# Charger.net
KiCad netlist of a schematic drawn in Altium Designer
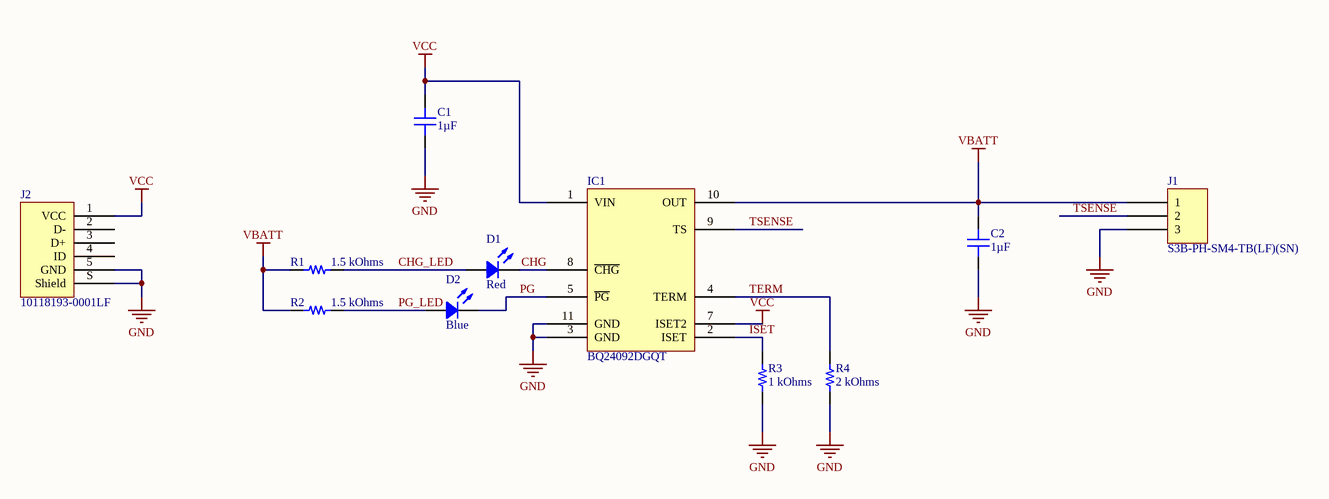
[diagram p0: Charger.SchDoc]

(export (version "E")
  (design (tool "Eeschema 10.0.6"))
  (components
    (comp (ref "C1")
      (value "1µF")
      (footprint "CAP 0603_1608")
      (description "CAP CER 1UF 25V X5R 0603")
      (fields (field (name "PART NUMBER") "CC0603KRX5R8BB105") (field (name "MANUFACTURER") "Yageo"))
      (libsource (lib "Celestial Altium Library - altium_library") (part "Capacitor"))
    )
    (comp (ref "C2")
      (value "1µF")
      (footprint "CAP 0603_1608")
      (description "CAP CER 1UF 25V X5R 0603")
      (fields (field (name "PART NUMBER") "CC0603KRX5R8BB105") (field (name "MANUFACTURER") "Yageo"))
      (libsource (lib "Celestial Altium Library - altium_library") (part "Capacitor"))
    )
    (comp (ref "D1")
      (value "Red")
      (footprint "LED 0603_1608 RED")
      (description "LED RED CLEAR 2SMD")
      (fields
        (field (name "PART NUMBER") "19-213USRC/S259/TR8")
        (field (name "MANUFACTURER") "Everlight Electronics Co Ltd")
      )
      (libsource (lib "Celestial Altium Library - altium_library") (part "LED"))
    )
    (comp (ref "D2")
      (value "Blue")
      (footprint "LED 0603_1608 BLUE")
      (description "LED BLUE CLEAR 2SMD")
      (fields
        (field (name "PART NUMBER") "EAST16084BA8")
        (field (name "MANUFACTURER") "Everlight Electronics Co Ltd")
      )
      (libsource (lib "Celestial Altium Library - altium_library") (part "LED"))
    )
    (comp (ref "IC1")
      (value "BQ24092DGQT")
      (footprint "TI PDSO-10 DCQ")
      (description "IC BATT CHARGER LI-ION 10MSOP")
      (fields (field (name "MANUFACTURER") "Texas Instruments"))
      (libsource (lib "Celestial Altium Library - altium_library") (part "TI BQ2409x"))
    )
    (comp (ref "J1")
      (value "S3B-PH-SM4-TB(LF)(SN)")
      (footprint "JST S3B-PH-SM4-TB")
      (description "CONN HEADER SMD R/A 3POS 2MM")
      (fields (field (name "MANUFACTURER") "JST Sales America Inc."))
      (libsource (lib "Celestial Altium Library - altium_library") (part "3 Pin"))
    )
    (comp (ref "J2")
      (value "10118193-0001LF")
      (footprint "FCI USB 10118193-0001LF")
      (description "CONN RCPT USB2.0 MICRO B SMD R/A")
      (fields (field (name "MANUFACTURER") "Amphenol ICC (FCI)"))
      (libsource (lib "Celestial Altium Library - altium_library") (part "USB 2.0 Type B Micro"))
    )
    (comp (ref "R1")
      (value "1.5 kOhms")
      (footprint "RES 0603_1608")
      (description "RES SMD 1.5K OHM 1% 1/10W 0603")
      (fields
        (field (name "PART NUMBER") "ERJ-3EKF1501V")
        (field (name "MANUFACTURER") "Panasonic Electronic Components")
      )
      (libsource (lib "Celestial Altium Library - altium_library") (part "Resistor"))
    )
    (comp (ref "R2")
      (value "1.5 kOhms")
      (footprint "RES 0603_1608")
      (description "RES SMD 1.5K OHM 1% 1/10W 0603")
      (fields
        (field (name "PART NUMBER") "ERJ-3EKF1501V")
        (field (name "MANUFACTURER") "Panasonic Electronic Components")
      )
      (libsource (lib "Celestial Altium Library - altium_library") (part "Resistor"))
    )
    (comp (ref "R3")
      (value "1 kOhms")
      (footprint "RES 0603_1608")
      (description "RES SMD 1K OHM 5% 1/4W 0603")
      (fields
        (field (name "PART NUMBER") "ERJ-PA3J102V")
        (field (name "MANUFACTURER") "Panasonic Electronic Components")
      )
      (libsource (lib "Celestial Altium Library - altium_library") (part "Resistor"))
    )
    (comp (ref "R4")
      (value "2 kOhms")
      (footprint "RES 0603_1608")
      (description "RES SMD 2K OHM 5% 1/4W 0603")
      (fields
        (field (name "PART NUMBER") "ERJ-PA3J202V")
        (field (name "MANUFACTURER") "Panasonic Electronic Components")
      )
      (libsource (lib "Celestial Altium Library - altium_library") (part "Resistor"))
    )
  )
  (nets
    (net (code "1") (name "/CHG") (class "Default")
      (node (ref "D1") (pin "2") (pinfunction "2_2") (pintype "passive"))
      (node (ref "IC1") (pin "8") (pinfunction "~{CHG}_8") (pintype "passive"))
    )
    (net (code "2") (name "/CHG_LED") (class "Default")
      (node (ref "D1") (pin "1") (pinfunction "1_1") (pintype "passive"))
      (node (ref "R1") (pin "2") (pinfunction "2_2") (pintype "passive"))
    )
    (net (code "3") (name "/ISET") (class "Default")
      (node (ref "IC1") (pin "2") (pinfunction "ISET_2") (pintype "passive"))
      (node (ref "R3") (pin "2") (pinfunction "2_2") (pintype "passive"))
    )
    (net (code "4") (name "/PG") (class "Default")
      (node (ref "D2") (pin "2") (pinfunction "2_2") (pintype "passive"))
      (node (ref "IC1") (pin "5") (pinfunction "~{PG}_5") (pintype "passive"))
    )
    (net (code "5") (name "/PG_LED") (class "Default")
      (node (ref "D2") (pin "1") (pinfunction "1_1") (pintype "passive"))
      (node (ref "R2") (pin "2") (pinfunction "2_2") (pintype "passive"))
    )
    (net (code "6") (name "/TERM") (class "Default")
      (node (ref "IC1") (pin "4") (pinfunction "TERM_4") (pintype "passive"))
      (node (ref "R4") (pin "2") (pinfunction "2_2") (pintype "passive"))
    )
    (net (code "7") (name "/TSENSE") (class "Default")
      (node (ref "IC1") (pin "9") (pinfunction "TS_9") (pintype "passive"))
      (node (ref "J1") (pin "2") (pinfunction "2_2") (pintype "passive"))
    )
    (net (code "8") (name "GND") (class "Default")
      (node (ref "C1") (pin "1") (pinfunction "1_1") (pintype "passive"))
      (node (ref "C2") (pin "1") (pinfunction "1_1") (pintype "passive"))
      (node (ref "IC1") (pin "11") (pinfunction "GND_11") (pintype "passive"))
      (node (ref "IC1") (pin "3") (pinfunction "GND_3") (pintype "passive"))
      (node (ref "J1") (pin "3") (pinfunction "3_3") (pintype "passive"))
      (node (ref "J2") (pin "5") (pinfunction "GND_5") (pintype "passive"))
      (node (ref "J2") (pin "S") (pinfunction "Shield_S") (pintype "passive"))
      (node (ref "R3") (pin "1") (pinfunction "1_1") (pintype "passive"))
      (node (ref "R4") (pin "1") (pinfunction "1_1") (pintype "passive"))
    )
    (net (code "9") (name "VBATT") (class "Default")
      (node (ref "C2") (pin "2") (pinfunction "2_2") (pintype "passive"))
      (node (ref "IC1") (pin "10") (pinfunction "OUT_10") (pintype "passive"))
      (node (ref "J1") (pin "1") (pinfunction "1_1") (pintype "passive"))
      (node (ref "R1") (pin "1") (pinfunction "1_1") (pintype "passive"))
      (node (ref "R2") (pin "1") (pinfunction "1_1") (pintype "passive"))
    )
    (net (code "10") (name "VCC") (class "Default")
      (node (ref "C1") (pin "2") (pinfunction "2_2") (pintype "passive"))
      (node (ref "IC1") (pin "1") (pinfunction "VIN_1") (pintype "passive"))
      (node (ref "IC1") (pin "7") (pinfunction "ISET2_7") (pintype "passive"))
      (node (ref "J2") (pin "1") (pinfunction "VCC_1") (pintype "passive"))
    )
    (net (code "11") (name "unconnected-(J2-D+-Pad3)") (class "Default")
      (node (ref "J2") (pin "3") (pinfunction "D+_3") (pintype "passive"))
    )
    (net (code "12") (name "unconnected-(J2-D--Pad2)") (class "Default")
      (node (ref "J2") (pin "2") (pinfunction "D-_2") (pintype "passive"))
    )
    (net (code "13") (name "unconnected-(J2-ID-Pad4)") (class "Default")
      (node (ref "J2") (pin "4") (pinfunction "ID_4") (pintype "passive"))
    )
  )
)
